# lv_io_solenoid_ctl.net
KiCad netlist of a schematic drawn in Altium Designer
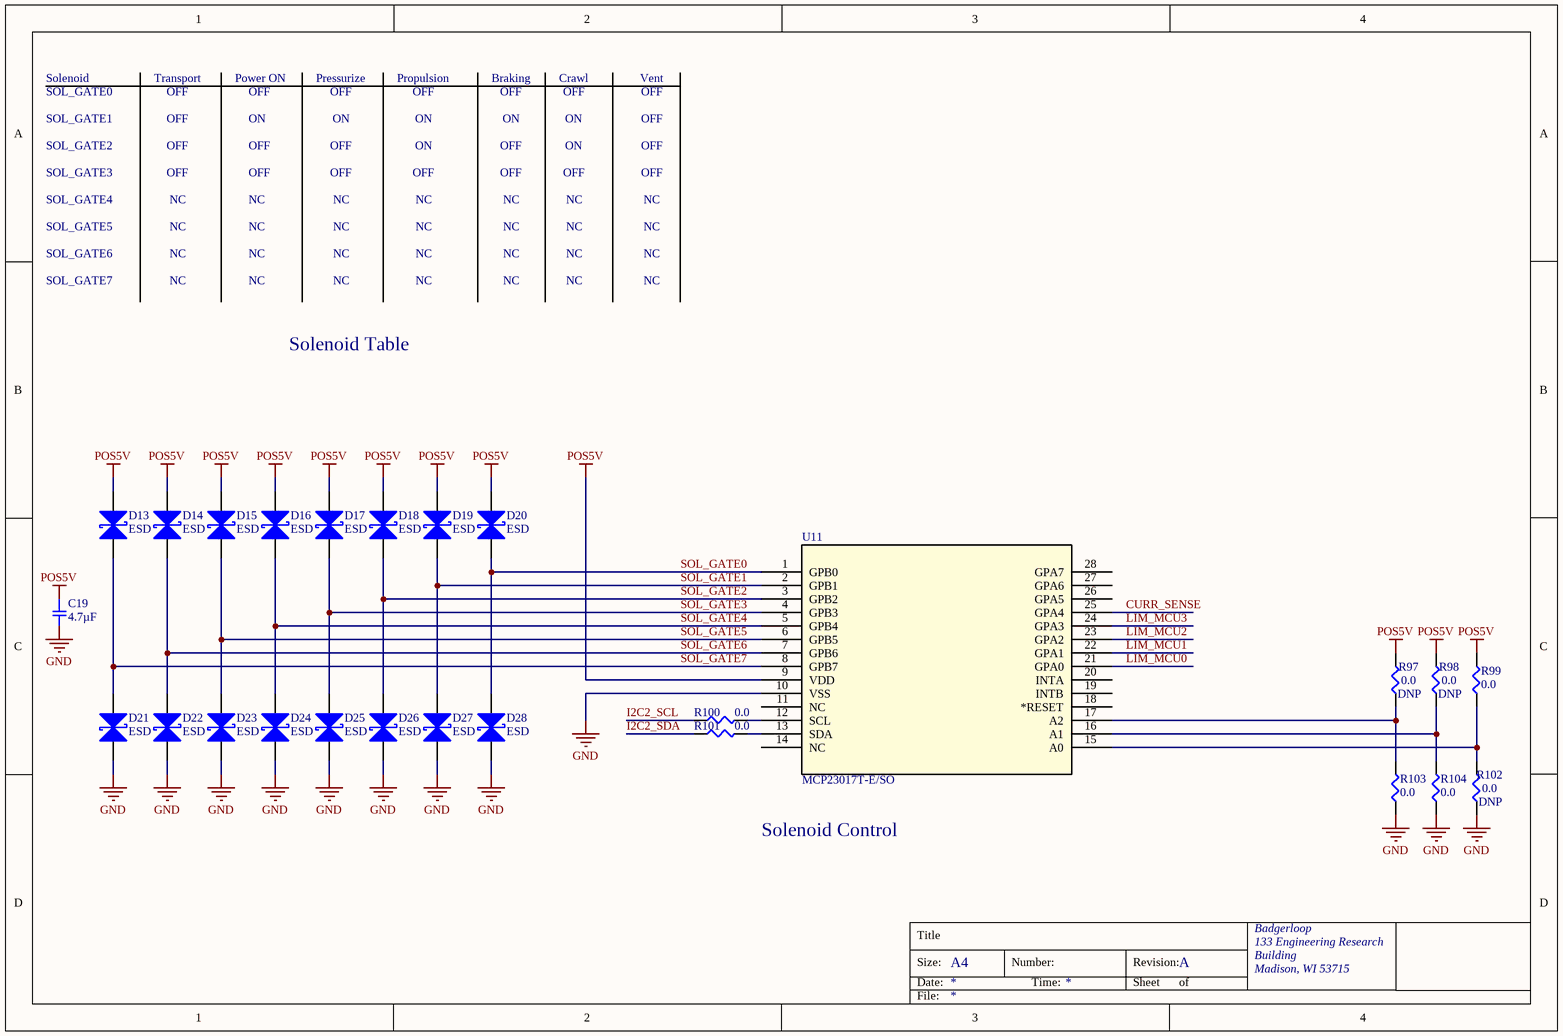
[diagram p0: lv_io_solenoid_ctl.SchDoc]

(export (version "E")
  (design (tool "Eeschema 10.0.6"))
  (components
    (comp (ref "C19")
      (value "4.7µF")
      (footprint "SMD-0805C")
      (description "CAP CER 4.7UF 6.3V X5R 0805")
      (fields
        (field (name "DIGI-KEY PART NUMBER") "490-9749-1-ND")
        (field (name "PART NUMBER") "GRM21BR60J475KA11L")
      )
      (libsource (lib "capacitor") (part "GRM21BR60J475KA11L"))
    )
    (comp (ref "D13")
      (value "ESD")
      (footprint "SMD-0402-RES")
      (description "ESD Supressor")
      (fields (field (name "MANUFACTURER") "EZAEG"))
      (libsource (lib "misc") (part "ESD Diode"))
    )
    (comp (ref "D14")
      (value "ESD")
      (footprint "SMD-0402-RES")
      (description "ESD Supressor")
      (fields (field (name "MANUFACTURER") "EZAEG"))
      (libsource (lib "misc") (part "ESD Diode"))
    )
    (comp (ref "D15")
      (value "ESD")
      (footprint "SMD-0402-RES")
      (description "ESD Supressor")
      (fields (field (name "MANUFACTURER") "EZAEG"))
      (libsource (lib "misc") (part "ESD Diode"))
    )
    (comp (ref "D16")
      (value "ESD")
      (footprint "SMD-0402-RES")
      (description "ESD Supressor")
      (fields (field (name "MANUFACTURER") "EZAEG"))
      (libsource (lib "misc") (part "ESD Diode"))
    )
    (comp (ref "D17")
      (value "ESD")
      (footprint "SMD-0402-RES")
      (description "ESD Supressor")
      (fields (field (name "MANUFACTURER") "EZAEG"))
      (libsource (lib "misc") (part "ESD Diode"))
    )
    (comp (ref "D18")
      (value "ESD")
      (footprint "SMD-0402-RES")
      (description "ESD Supressor")
      (fields (field (name "MANUFACTURER") "EZAEG"))
      (libsource (lib "misc") (part "ESD Diode"))
    )
    (comp (ref "D19")
      (value "ESD")
      (footprint "SMD-0402-RES")
      (description "ESD Supressor")
      (fields (field (name "MANUFACTURER") "EZAEG"))
      (libsource (lib "misc") (part "ESD Diode"))
    )
    (comp (ref "D20")
      (value "ESD")
      (footprint "SMD-0402-RES")
      (description "ESD Supressor")
      (fields (field (name "MANUFACTURER") "EZAEG"))
      (libsource (lib "misc") (part "ESD Diode"))
    )
    (comp (ref "D21")
      (value "ESD")
      (footprint "SMD-0402-RES")
      (description "ESD Supressor")
      (fields (field (name "MANUFACTURER") "EZAEG"))
      (libsource (lib "misc") (part "ESD Diode"))
    )
    (comp (ref "D22")
      (value "ESD")
      (footprint "SMD-0402-RES")
      (description "ESD Supressor")
      (fields (field (name "MANUFACTURER") "EZAEG"))
      (libsource (lib "misc") (part "ESD Diode"))
    )
    (comp (ref "D23")
      (value "ESD")
      (footprint "SMD-0402-RES")
      (description "ESD Supressor")
      (fields (field (name "MANUFACTURER") "EZAEG"))
      (libsource (lib "misc") (part "ESD Diode"))
    )
    (comp (ref "D24")
      (value "ESD")
      (footprint "SMD-0402-RES")
      (description "ESD Supressor")
      (fields (field (name "MANUFACTURER") "EZAEG"))
      (libsource (lib "misc") (part "ESD Diode"))
    )
    (comp (ref "D25")
      (value "ESD")
      (footprint "SMD-0402-RES")
      (description "ESD Supressor")
      (fields (field (name "MANUFACTURER") "EZAEG"))
      (libsource (lib "misc") (part "ESD Diode"))
    )
    (comp (ref "D26")
      (value "ESD")
      (footprint "SMD-0402-RES")
      (description "ESD Supressor")
      (fields (field (name "MANUFACTURER") "EZAEG"))
      (libsource (lib "misc") (part "ESD Diode"))
    )
    (comp (ref "D27")
      (value "ESD")
      (footprint "SMD-0402-RES")
      (description "ESD Supressor")
      (fields (field (name "MANUFACTURER") "EZAEG"))
      (libsource (lib "misc") (part "ESD Diode"))
    )
    (comp (ref "D28")
      (value "ESD")
      (footprint "SMD-0402-RES")
      (description "ESD Supressor")
      (fields (field (name "MANUFACTURER") "EZAEG"))
      (libsource (lib "misc") (part "ESD Diode"))
    )
    (comp (ref "R97")
      (value "0.0")
      (footprint "SMD-0402-RES")
      (description "RES SMD 0.0OHM JUMPER 1/10W 0402")
      (fields
        (field (name "PART NUMBER") "ERJ-2GE0R00X")
        (field (name "DIGI-KEY PART NUMBER") "P0.0JCT-ND")
        (field (name "DNP") "DNP")
      )
      (libsource (lib "resistor") (part "ERJ-2GE0R00X"))
    )
    (comp (ref "R98")
      (value "0.0")
      (footprint "SMD-0402-RES")
      (description "RES SMD 0.0OHM JUMPER 1/10W 0402")
      (fields
        (field (name "PART NUMBER") "ERJ-2GE0R00X")
        (field (name "DIGI-KEY PART NUMBER") "P0.0JCT-ND")
        (field (name "DNP") "DNP")
      )
      (libsource (lib "resistor") (part "ERJ-2GE0R00X"))
    )
    (comp (ref "R99")
      (value "0.0")
      (footprint "SMD-0402-RES")
      (description "RES SMD 0.0OHM JUMPER 1/10W 0402")
      (fields (field (name "PART NUMBER") "ERJ-2GE0R00X") (field (name "DIGI-KEY PART NUMBER") "P0.0JCT-ND"))
      (libsource (lib "resistor") (part "ERJ-2GE0R00X"))
    )
    (comp (ref "R100")
      (value "0.0")
      (footprint "SMD-0402-RES")
      (description "RES SMD 0.0OHM JUMPER 1/10W 0402")
      (fields (field (name "PART NUMBER") "ERJ-2GE0R00X") (field (name "DIGI-KEY PART NUMBER") "P0.0JCT-ND"))
      (libsource (lib "resistor") (part "ERJ-2GE0R00X"))
    )
    (comp (ref "R101")
      (value "0.0")
      (footprint "SMD-0402-RES")
      (description "RES SMD 0.0OHM JUMPER 1/10W 0402")
      (fields (field (name "PART NUMBER") "ERJ-2GE0R00X") (field (name "DIGI-KEY PART NUMBER") "P0.0JCT-ND"))
      (libsource (lib "resistor") (part "ERJ-2GE0R00X"))
    )
    (comp (ref "R102")
      (value "0.0")
      (footprint "SMD-0402-RES")
      (description "RES SMD 0.0OHM JUMPER 1/10W 0402")
      (fields
        (field (name "PART NUMBER") "ERJ-2GE0R00X")
        (field (name "DIGI-KEY PART NUMBER") "P0.0JCT-ND")
        (field (name "DNP") "DNP")
      )
      (libsource (lib "resistor") (part "ERJ-2GE0R00X"))
    )
    (comp (ref "R103")
      (value "0.0")
      (footprint "SMD-0402-RES")
      (description "RES SMD 0.0OHM JUMPER 1/10W 0402")
      (fields (field (name "PART NUMBER") "ERJ-2GE0R00X") (field (name "DIGI-KEY PART NUMBER") "P0.0JCT-ND"))
      (libsource (lib "resistor") (part "ERJ-2GE0R00X"))
    )
    (comp (ref "R104")
      (value "0.0")
      (footprint "SMD-0402-RES")
      (description "RES SMD 0.0OHM JUMPER 1/10W 0402")
      (fields (field (name "PART NUMBER") "ERJ-2GE0R00X") (field (name "DIGI-KEY PART NUMBER") "P0.0JCT-ND"))
      (libsource (lib "resistor") (part "ERJ-2GE0R00X"))
    )
    (comp (ref "U11")
      (value "MCP23017T-E/SO")
      (footprint "SOIC28-W_MC-M")
      (description "IC I/O EXPANDER I2C 16B 28SOIC")
      (fields (field (name "MANUFACTURER") "Microchip"))
      (libsource (lib "ic") (part "MCP23017T-E/SO"))
    )
  )
  (nets
    (net (code "1") (name "/CURR_SENSE") (class "Default")
      (node (ref "U11") (pin "25") (pinfunction "GPA4_25") (pintype "passive"))
    )
    (net (code "2") (name "/I2C2_SCL") (class "Default")
      (node (ref "R100") (pin "1") (pinfunction "1_1") (pintype "passive"))
    )
    (net (code "3") (name "/I2C2_SDA") (class "Default")
      (node (ref "R101") (pin "1") (pinfunction "1_1") (pintype "passive"))
    )
    (net (code "4") (name "/LIM_MCU0") (class "Default")
      (node (ref "U11") (pin "21") (pinfunction "GPA0_21") (pintype "passive"))
    )
    (net (code "5") (name "/LIM_MCU1") (class "Default")
      (node (ref "U11") (pin "22") (pinfunction "GPA1_22") (pintype "passive"))
    )
    (net (code "6") (name "/LIM_MCU2") (class "Default")
      (node (ref "U11") (pin "23") (pinfunction "GPA2_23") (pintype "passive"))
    )
    (net (code "7") (name "/LIM_MCU3") (class "Default")
      (node (ref "U11") (pin "24") (pinfunction "GPA3_24") (pintype "passive"))
    )
    (net (code "8") (name "/SOL_GATE0") (class "Default")
      (node (ref "D20") (pin "1") (pinfunction "A_1") (pintype "passive"))
      (node (ref "D28") (pin "2") (pinfunction "K_2") (pintype "passive"))
      (node (ref "U11") (pin "1") (pinfunction "GPB0_1") (pintype "passive"))
    )
    (net (code "9") (name "/SOL_GATE1") (class "Default")
      (node (ref "D19") (pin "1") (pinfunction "A_1") (pintype "passive"))
      (node (ref "D27") (pin "2") (pinfunction "K_2") (pintype "passive"))
      (node (ref "U11") (pin "2") (pinfunction "GPB1_2") (pintype "passive"))
    )
    (net (code "10") (name "/SOL_GATE2") (class "Default")
      (node (ref "D18") (pin "1") (pinfunction "A_1") (pintype "passive"))
      (node (ref "D26") (pin "2") (pinfunction "K_2") (pintype "passive"))
      (node (ref "U11") (pin "3") (pinfunction "GPB2_3") (pintype "passive"))
    )
    (net (code "11") (name "/SOL_GATE3") (class "Default")
      (node (ref "D17") (pin "1") (pinfunction "A_1") (pintype "passive"))
      (node (ref "D25") (pin "2") (pinfunction "K_2") (pintype "passive"))
      (node (ref "U11") (pin "4") (pinfunction "GPB3_4") (pintype "passive"))
    )
    (net (code "12") (name "/SOL_GATE4") (class "Default")
      (node (ref "D16") (pin "1") (pinfunction "A_1") (pintype "passive"))
      (node (ref "D24") (pin "2") (pinfunction "K_2") (pintype "passive"))
      (node (ref "U11") (pin "5") (pinfunction "GPB4_5") (pintype "passive"))
    )
    (net (code "13") (name "/SOL_GATE5") (class "Default")
      (node (ref "D15") (pin "1") (pinfunction "A_1") (pintype "passive"))
      (node (ref "D23") (pin "2") (pinfunction "K_2") (pintype "passive"))
      (node (ref "U11") (pin "6") (pinfunction "GPB5_6") (pintype "passive"))
    )
    (net (code "14") (name "/SOL_GATE6") (class "Default")
      (node (ref "D14") (pin "1") (pinfunction "A_1") (pintype "passive"))
      (node (ref "D22") (pin "2") (pinfunction "K_2") (pintype "passive"))
      (node (ref "U11") (pin "7") (pinfunction "GPB6_7") (pintype "passive"))
    )
    (net (code "15") (name "/SOL_GATE7") (class "Default")
      (node (ref "D13") (pin "1") (pinfunction "A_1") (pintype "passive"))
      (node (ref "D21") (pin "2") (pinfunction "K_2") (pintype "passive"))
      (node (ref "U11") (pin "8") (pinfunction "GPB7_8") (pintype "passive"))
    )
    (net (code "16") (name "GND") (class "Default")
      (node (ref "C19") (pin "2") (pinfunction "2_2") (pintype "passive"))
      (node (ref "D21") (pin "1") (pinfunction "A_1") (pintype "passive"))
      (node (ref "D22") (pin "1") (pinfunction "A_1") (pintype "passive"))
      (node (ref "D23") (pin "1") (pinfunction "A_1") (pintype "passive"))
      (node (ref "D24") (pin "1") (pinfunction "A_1") (pintype "passive"))
      (node (ref "D25") (pin "1") (pinfunction "A_1") (pintype "passive"))
      (node (ref "D26") (pin "1") (pinfunction "A_1") (pintype "passive"))
      (node (ref "D27") (pin "1") (pinfunction "A_1") (pintype "passive"))
      (node (ref "D28") (pin "1") (pinfunction "A_1") (pintype "passive"))
      (node (ref "R102") (pin "1") (pinfunction "1_1") (pintype "passive"))
      (node (ref "R103") (pin "1") (pinfunction "1_1") (pintype "passive"))
      (node (ref "R104") (pin "1") (pinfunction "1_1") (pintype "passive"))
      (node (ref "U11") (pin "10") (pinfunction "VSS_10") (pintype "passive"))
    )
    (net (code "17") (name "Net-(U11-A0)") (class "Default")
      (node (ref "R102") (pin "2") (pinfunction "2_2") (pintype "passive"))
      (node (ref "R99") (pin "1") (pinfunction "1_1") (pintype "passive"))
      (node (ref "U11") (pin "15") (pinfunction "A0_15") (pintype "passive"))
    )
    (net (code "18") (name "Net-(U11-A1)") (class "Default")
      (node (ref "R104") (pin "2") (pinfunction "2_2") (pintype "passive"))
      (node (ref "R98") (pin "1") (pinfunction "1_1") (pintype "passive"))
      (node (ref "U11") (pin "16") (pinfunction "A1_16") (pintype "passive"))
    )
    (net (code "19") (name "Net-(U11-A2)") (class "Default")
      (node (ref "R103") (pin "2") (pinfunction "2_2") (pintype "passive"))
      (node (ref "R97") (pin "1") (pinfunction "1_1") (pintype "passive"))
      (node (ref "U11") (pin "17") (pinfunction "A2_17") (pintype "passive"))
    )
    (net (code "20") (name "Net-(U11-SCL)") (class "Default")
      (node (ref "R100") (pin "2") (pinfunction "2_2") (pintype "passive"))
      (node (ref "U11") (pin "12") (pinfunction "SCL_12") (pintype "passive"))
    )
    (net (code "21") (name "Net-(U11-SDA)") (class "Default")
      (node (ref "R101") (pin "2") (pinfunction "2_2") (pintype "passive"))
      (node (ref "U11") (pin "13") (pinfunction "SDA_13") (pintype "passive"))
    )
    (net (code "22") (name "POS5V") (class "Default")
      (node (ref "C19") (pin "1") (pinfunction "1_1") (pintype "passive"))
      (node (ref "D13") (pin "2") (pinfunction "K_2") (pintype "passive"))
      (node (ref "D14") (pin "2") (pinfunction "K_2") (pintype "passive"))
      (node (ref "D15") (pin "2") (pinfunction "K_2") (pintype "passive"))
      (node (ref "D16") (pin "2") (pinfunction "K_2") (pintype "passive"))
      (node (ref "D17") (pin "2") (pinfunction "K_2") (pintype "passive"))
      (node (ref "D18") (pin "2") (pinfunction "K_2") (pintype "passive"))
      (node (ref "D19") (pin "2") (pinfunction "K_2") (pintype "passive"))
      (node (ref "D20") (pin "2") (pinfunction "K_2") (pintype "passive"))
      (node (ref "R97") (pin "2") (pinfunction "2_2") (pintype "passive"))
      (node (ref "R98") (pin "2") (pinfunction "2_2") (pintype "passive"))
      (node (ref "R99") (pin "2") (pinfunction "2_2") (pintype "passive"))
      (node (ref "U11") (pin "9") (pinfunction "VDD_9") (pintype "passive"))
    )
    (net (code "23") (name "unconnected-(U11-*RESET-Pad18)") (class "Default")
      (node (ref "U11") (pin "18") (pinfunction "*RESET_18") (pintype "passive"))
    )
    (net (code "24") (name "unconnected-(U11-GPA5-Pad26)") (class "Default")
      (node (ref "U11") (pin "26") (pinfunction "GPA5_26") (pintype "passive"))
    )
    (net (code "25") (name "unconnected-(U11-GPA6-Pad27)") (class "Default")
      (node (ref "U11") (pin "27") (pinfunction "GPA6_27") (pintype "passive"))
    )
    (net (code "26") (name "unconnected-(U11-GPA7-Pad28)") (class "Default")
      (node (ref "U11") (pin "28") (pinfunction "GPA7_28") (pintype "passive"))
    )
    (net (code "27") (name "unconnected-(U11-INTA-Pad20)") (class "Default")
      (node (ref "U11") (pin "20") (pinfunction "INTA_20") (pintype "passive"))
    )
    (net (code "28") (name "unconnected-(U11-INTB-Pad19)") (class "Default")
      (node (ref "U11") (pin "19") (pinfunction "INTB_19") (pintype "passive"))
    )
    (net (code "29") (name "unconnected-(U11-NC-Pad11)") (class "Default")
      (node (ref "U11") (pin "11") (pinfunction "NC_11") (pintype "passive"))
    )
    (net (code "30") (name "unconnected-(U11-NC-Pad14)") (class "Default")
      (node (ref "U11") (pin "14") (pinfunction "NC_14") (pintype "passive"))
    )
  )
)
